# 02_-Thermistors.net
KiCad netlist of a schematic drawn in Altium Designer
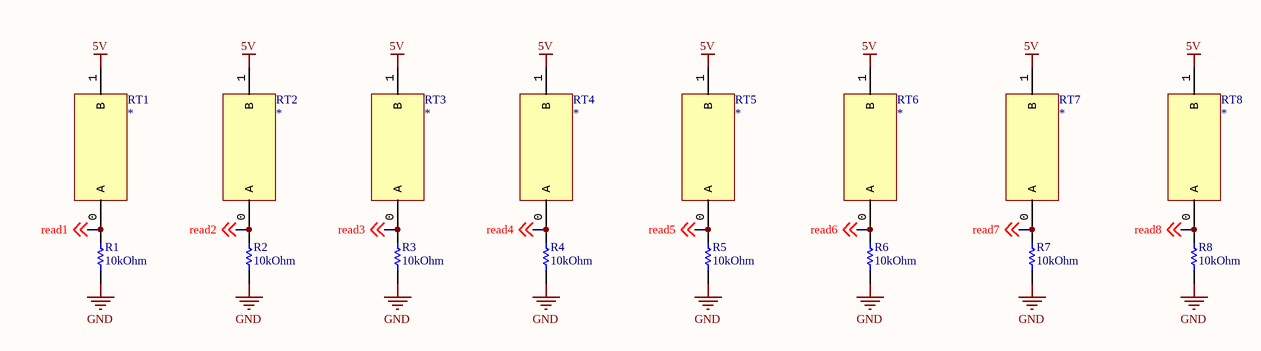
[diagram p0: [02]-Thermistors.SchDoc]

(export (version "E")
  (design (tool "Eeschema 10.0.6"))
  (components
    (comp (ref "R1")
      (value "10kOhm")
      (footprint "RESC2013X60X35LL10T20")
      (description "RES 10.0K OHM 1/8W 1% 0805 SMD")
      (fields (field (name "MPN") "RC0805FR-0710KL") (field (name "MANUFACTURER") "Yageo"))
      (libsource (lib "Altium Content Vault") (part "RES-2"))
    )
    (comp (ref "R2")
      (value "10kOhm")
      (footprint "RESC2013X60X35LL10T20")
      (description "RES 10.0K OHM 1/8W 1% 0805 SMD")
      (fields (field (name "MPN") "RC0805FR-0710KL") (field (name "MANUFACTURER") "Yageo"))
      (libsource (lib "Altium Content Vault") (part "RES-2"))
    )
    (comp (ref "R3")
      (value "10kOhm")
      (footprint "RESC2013X60X35LL10T20")
      (description "RES 10.0K OHM 1/8W 1% 0805 SMD")
      (fields (field (name "MPN") "RC0805FR-0710KL") (field (name "MANUFACTURER") "Yageo"))
      (libsource (lib "Altium Content Vault") (part "RES-2"))
    )
    (comp (ref "R4")
      (value "10kOhm")
      (footprint "RESC2013X60X35LL10T20")
      (description "RES 10.0K OHM 1/8W 1% 0805 SMD")
      (fields (field (name "MPN") "RC0805FR-0710KL") (field (name "MANUFACTURER") "Yageo"))
      (libsource (lib "Altium Content Vault") (part "RES-2"))
    )
    (comp (ref "R5")
      (value "10kOhm")
      (footprint "RESC2013X60X35LL10T20")
      (description "RES 10.0K OHM 1/8W 1% 0805 SMD")
      (fields (field (name "MPN") "RC0805FR-0710KL") (field (name "MANUFACTURER") "Yageo"))
      (libsource (lib "Altium Content Vault") (part "RES-2"))
    )
    (comp (ref "R6")
      (value "10kOhm")
      (footprint "RESC2013X60X35LL10T20")
      (description "RES 10.0K OHM 1/8W 1% 0805 SMD")
      (fields (field (name "MPN") "RC0805FR-0710KL") (field (name "MANUFACTURER") "Yageo"))
      (libsource (lib "Altium Content Vault") (part "RES-2"))
    )
    (comp (ref "R7")
      (value "10kOhm")
      (footprint "RESC2013X60X35LL10T20")
      (description "RES 10.0K OHM 1/8W 1% 0805 SMD")
      (fields (field (name "MPN") "RC0805FR-0710KL") (field (name "MANUFACTURER") "Yageo"))
      (libsource (lib "Altium Content Vault") (part "RES-2"))
    )
    (comp (ref "R8")
      (value "10kOhm")
      (footprint "RESC2013X60X35LL10T20")
      (description "RES 10.0K OHM 1/8W 1% 0805 SMD")
      (fields (field (name "MPN") "RC0805FR-0710KL") (field (name "MANUFACTURER") "Yageo"))
      (libsource (lib "Altium Content Vault") (part "RES-2"))
    )
    (comp (ref "RT1") (value "*") (footprint "thermistor") (libsource (lib "Schlib1") (part "thermistor")))
    (comp (ref "RT2") (value "*") (footprint "thermistor") (libsource (lib "Schlib1") (part "thermistor")))
    (comp (ref "RT3") (value "*") (footprint "thermistor") (libsource (lib "Schlib1") (part "thermistor")))
    (comp (ref "RT4") (value "*") (footprint "thermistor") (libsource (lib "Schlib1") (part "thermistor")))
    (comp (ref "RT5") (value "*") (footprint "thermistor") (libsource (lib "Schlib1") (part "thermistor")))
    (comp (ref "RT6") (value "*") (footprint "thermistor") (libsource (lib "Schlib1") (part "thermistor")))
    (comp (ref "RT7") (value "*") (footprint "thermistor") (libsource (lib "Schlib1") (part "thermistor")))
    (comp (ref "RT8") (value "*") (footprint "thermistor") (libsource (lib "Schlib1") (part "thermistor")))
  )
  (nets
    (net (code "1") (name "5V") (class "Default")
      (node (ref "RT1") (pin "1") (pinfunction "B_1") (pintype "passive"))
      (node (ref "RT2") (pin "1") (pinfunction "B_1") (pintype "passive"))
      (node (ref "RT3") (pin "1") (pinfunction "B_1") (pintype "passive"))
      (node (ref "RT4") (pin "1") (pinfunction "B_1") (pintype "passive"))
      (node (ref "RT5") (pin "1") (pinfunction "B_1") (pintype "passive"))
      (node (ref "RT6") (pin "1") (pinfunction "B_1") (pintype "passive"))
      (node (ref "RT7") (pin "1") (pinfunction "B_1") (pintype "passive"))
      (node (ref "RT8") (pin "1") (pinfunction "B_1") (pintype "passive"))
    )
    (net (code "2") (name "GND") (class "Default")
      (node (ref "R1") (pin "1") (pinfunction "1_1") (pintype "passive"))
      (node (ref "R2") (pin "1") (pinfunction "1_1") (pintype "passive"))
      (node (ref "R3") (pin "1") (pinfunction "1_1") (pintype "passive"))
      (node (ref "R4") (pin "1") (pinfunction "1_1") (pintype "passive"))
      (node (ref "R5") (pin "1") (pinfunction "1_1") (pintype "passive"))
      (node (ref "R6") (pin "1") (pinfunction "1_1") (pintype "passive"))
      (node (ref "R7") (pin "1") (pinfunction "1_1") (pintype "passive"))
      (node (ref "R8") (pin "1") (pinfunction "1_1") (pintype "passive"))
    )
    (net (code "3") (name "read1") (class "Default")
      (node (ref "R1") (pin "2") (pinfunction "2_2") (pintype "passive"))
      (node (ref "RT1") (pin "0") (pinfunction "A_0") (pintype "passive"))
    )
    (net (code "4") (name "read2") (class "Default")
      (node (ref "R2") (pin "2") (pinfunction "2_2") (pintype "passive"))
      (node (ref "RT2") (pin "0") (pinfunction "A_0") (pintype "passive"))
    )
    (net (code "5") (name "read3") (class "Default")
      (node (ref "R3") (pin "2") (pinfunction "2_2") (pintype "passive"))
      (node (ref "RT3") (pin "0") (pinfunction "A_0") (pintype "passive"))
    )
    (net (code "6") (name "read4") (class "Default")
      (node (ref "R4") (pin "2") (pinfunction "2_2") (pintype "passive"))
      (node (ref "RT4") (pin "0") (pinfunction "A_0") (pintype "passive"))
    )
    (net (code "7") (name "read5") (class "Default")
      (node (ref "R5") (pin "2") (pinfunction "2_2") (pintype "passive"))
      (node (ref "RT5") (pin "0") (pinfunction "A_0") (pintype "passive"))
    )
    (net (code "8") (name "read6") (class "Default")
      (node (ref "R6") (pin "2") (pinfunction "2_2") (pintype "passive"))
      (node (ref "RT6") (pin "0") (pinfunction "A_0") (pintype "passive"))
    )
    (net (code "9") (name "read7") (class "Default")
      (node (ref "R7") (pin "2") (pinfunction "2_2") (pintype "passive"))
      (node (ref "RT7") (pin "0") (pinfunction "A_0") (pintype "passive"))
    )
    (net (code "10") (name "read8") (class "Default")
      (node (ref "R8") (pin "2") (pinfunction "2_2") (pintype "passive"))
      (node (ref "RT8") (pin "0") (pinfunction "A_0") (pintype "passive"))
    )
  )
)
